# picotouch_synth.net
KiCad netlist of a schematic drawn in EAGLE
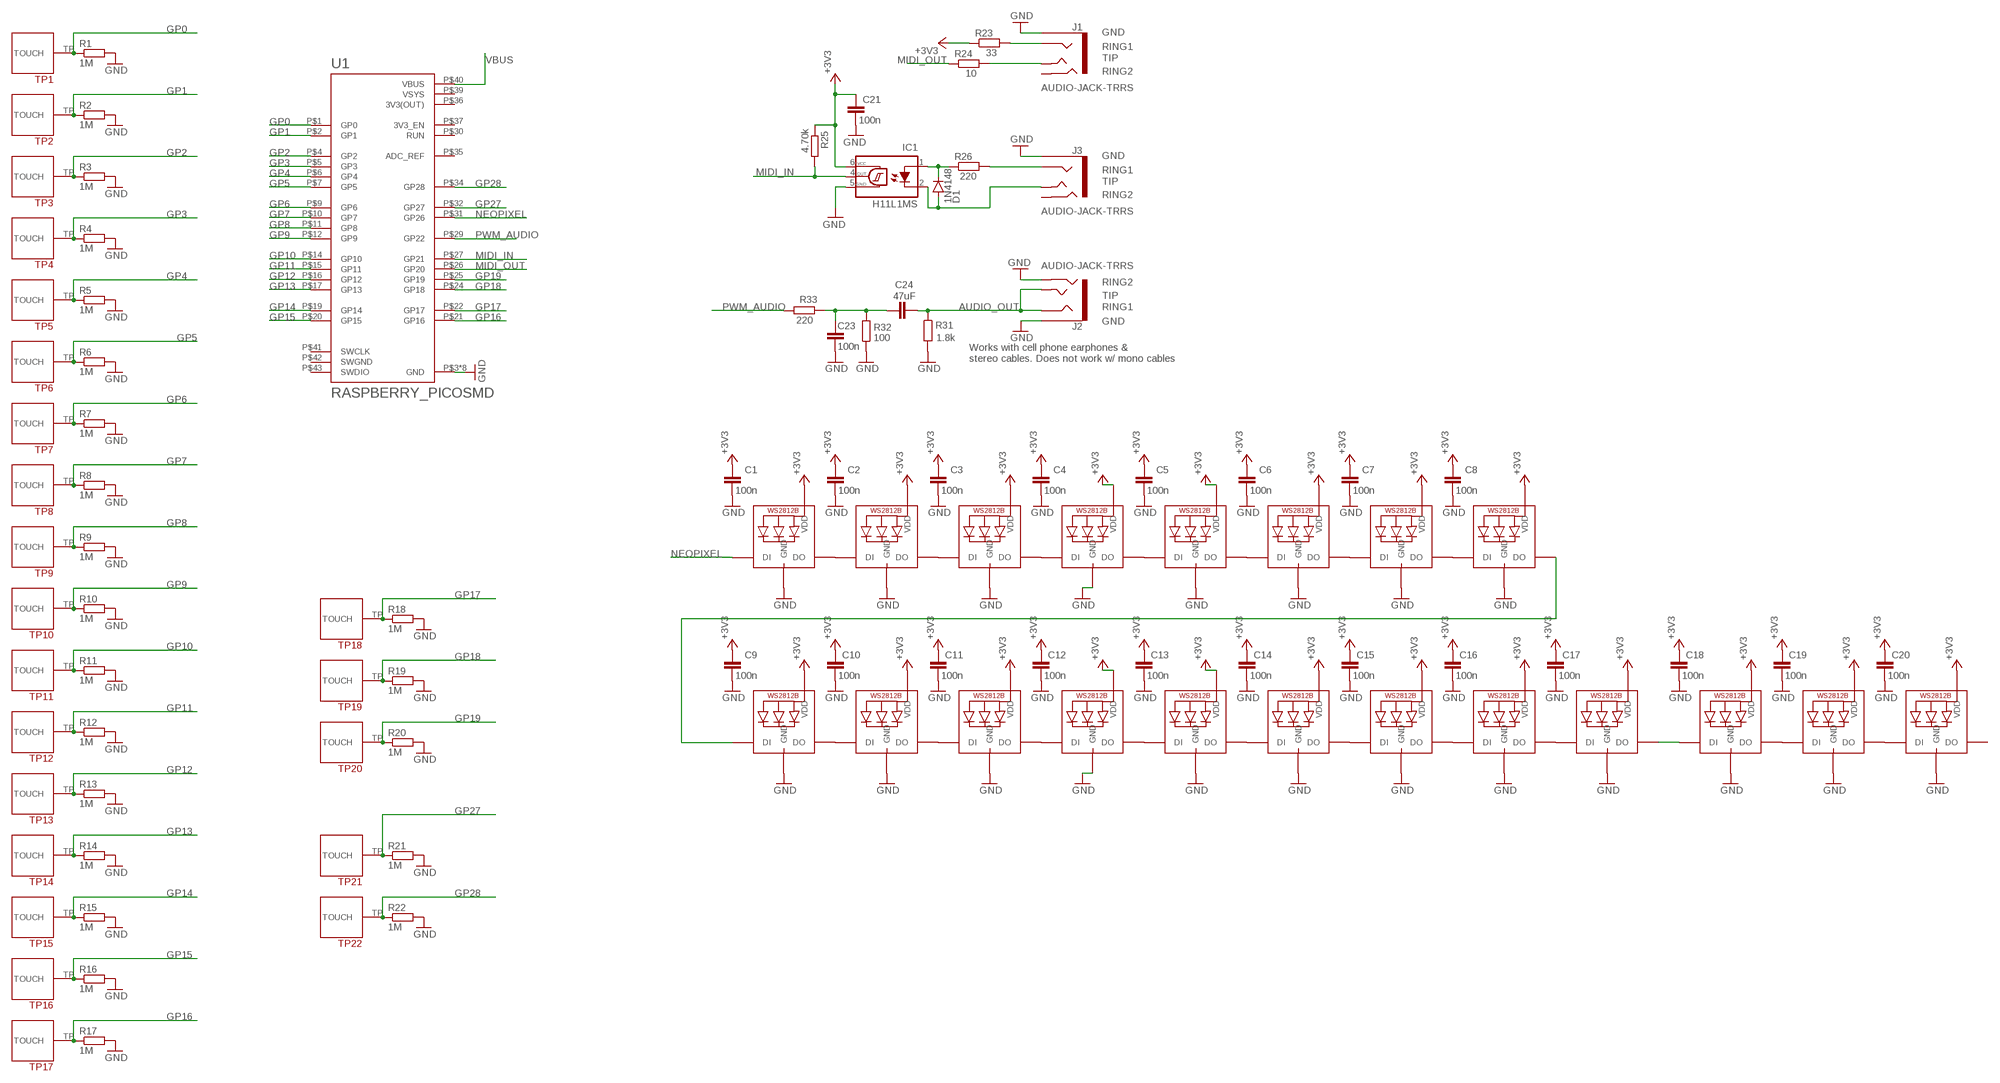
[diagram p0: schematic, sheet 1]

(export (version "E")
  (design (tool "Eeschema 10.0.6"))
  (components
    (comp (ref "C1")
      (value "100n")
      (footprint "eagle-import:C0603")
      (libsource (lib "eagle-import") (part "C-EUC0603"))
    )
    (comp (ref "C2")
      (value "100n")
      (footprint "eagle-import:C0603")
      (libsource (lib "eagle-import") (part "C-EUC0603"))
    )
    (comp (ref "C3")
      (value "100n")
      (footprint "eagle-import:C0603")
      (libsource (lib "eagle-import") (part "C-EUC0603"))
    )
    (comp (ref "C4")
      (value "100n")
      (footprint "eagle-import:C0603")
      (libsource (lib "eagle-import") (part "C-EUC0603"))
    )
    (comp (ref "C5")
      (value "100n")
      (footprint "eagle-import:C0603")
      (libsource (lib "eagle-import") (part "C-EUC0603"))
    )
    (comp (ref "C6")
      (value "100n")
      (footprint "eagle-import:C0603")
      (libsource (lib "eagle-import") (part "C-EUC0603"))
    )
    (comp (ref "C7")
      (value "100n")
      (footprint "eagle-import:C0603")
      (libsource (lib "eagle-import") (part "C-EUC0603"))
    )
    (comp (ref "C8")
      (value "100n")
      (footprint "eagle-import:C0603")
      (libsource (lib "eagle-import") (part "C-EUC0603"))
    )
    (comp (ref "C9")
      (value "100n")
      (footprint "eagle-import:C0603")
      (libsource (lib "eagle-import") (part "C-EUC0603"))
    )
    (comp (ref "C10")
      (value "100n")
      (footprint "eagle-import:C0603")
      (libsource (lib "eagle-import") (part "C-EUC0603"))
    )
    (comp (ref "C11")
      (value "100n")
      (footprint "eagle-import:C0603")
      (libsource (lib "eagle-import") (part "C-EUC0603"))
    )
    (comp (ref "C12")
      (value "100n")
      (footprint "eagle-import:C0603")
      (libsource (lib "eagle-import") (part "C-EUC0603"))
    )
    (comp (ref "C13")
      (value "100n")
      (footprint "eagle-import:C0603")
      (libsource (lib "eagle-import") (part "C-EUC0603"))
    )
    (comp (ref "C14")
      (value "100n")
      (footprint "eagle-import:C0603")
      (libsource (lib "eagle-import") (part "C-EUC0603"))
    )
    (comp (ref "C15")
      (value "100n")
      (footprint "eagle-import:C0603")
      (libsource (lib "eagle-import") (part "C-EUC0603"))
    )
    (comp (ref "C16")
      (value "100n")
      (footprint "eagle-import:C0603")
      (libsource (lib "eagle-import") (part "C-EUC0603"))
    )
    (comp (ref "C17")
      (value "100n")
      (footprint "eagle-import:C0603")
      (libsource (lib "eagle-import") (part "C-EUC0603"))
    )
    (comp (ref "C18")
      (value "100n")
      (footprint "eagle-import:C0603")
      (libsource (lib "eagle-import") (part "C-EUC0603"))
    )
    (comp (ref "C19")
      (value "100n")
      (footprint "eagle-import:C0603")
      (libsource (lib "eagle-import") (part "C-EUC0603"))
    )
    (comp (ref "C20")
      (value "100n")
      (footprint "eagle-import:C0603")
      (libsource (lib "eagle-import") (part "C-EUC0603"))
    )
    (comp (ref "C21")
      (value "100n")
      (footprint "eagle-import:C0603")
      (libsource (lib "eagle-import") (part "C-EUC0603"))
    )
    (comp (ref "C23")
      (value "100n")
      (footprint "eagle-import:C0603")
      (libsource (lib "eagle-import") (part "C-EUC0603"))
    )
    (comp (ref "C24")
      (value "47uF")
      (footprint "eagle-import:C0603")
      (libsource (lib "eagle-import") (part "C-EUC0603"))
    )
    (comp (ref "D1")
      (value "1N4148")
      (footprint "eagle-import:SOD123")
      (libsource (lib "eagle-import") (part "DIODE-SOD123"))
    )
    (comp (ref "IC1")
      (value "H11L1MS")
      (footprint "eagle-import:DIL6-SMD")
      (libsource (lib "eagle-import") (part "H11LMS1"))
    )
    (comp (ref "J1")
      (value "AUDIO-JACK-TRRS")
      (footprint "eagle-import:PJ-320D_SPARKFUN")
      (fields (field (name "MPN") "PJ-320D"))
      (libsource (lib "eagle-import") (part "AUDIO-JACK-TRRS"))
    )
    (comp (ref "J2")
      (value "AUDIO-JACK-TRRS")
      (footprint "eagle-import:PJ-320D_SPARKFUN")
      (fields (field (name "MPN") "PJ-320D") (field (name "LCSC") "C431535"))
      (libsource (lib "eagle-import") (part "AUDIO-JACK-TRRS"))
    )
    (comp (ref "J3")
      (value "AUDIO-JACK-TRRS")
      (footprint "eagle-import:PJ-320D_SPARKFUN")
      (fields (field (name "MPN") "PJ-320D"))
      (libsource (lib "eagle-import") (part "AUDIO-JACK-TRRS"))
    )
    (comp (ref "LED1")
      (value "WS2812B3535")
      (footprint "eagle-import:LED3535")
      (libsource (lib "eagle-import") (part "WS2812B3535"))
    )
    (comp (ref "LED2")
      (value "WS2812B3535")
      (footprint "eagle-import:LED3535")
      (libsource (lib "eagle-import") (part "WS2812B3535"))
    )
    (comp (ref "LED3")
      (value "WS2812B3535")
      (footprint "eagle-import:LED3535")
      (libsource (lib "eagle-import") (part "WS2812B3535"))
    )
    (comp (ref "LED4")
      (value "WS2812B3535")
      (footprint "eagle-import:LED3535")
      (libsource (lib "eagle-import") (part "WS2812B3535"))
    )
    (comp (ref "LED5")
      (value "WS2812B3535")
      (footprint "eagle-import:LED3535")
      (libsource (lib "eagle-import") (part "WS2812B3535"))
    )
    (comp (ref "LED6")
      (value "WS2812B3535")
      (footprint "eagle-import:LED3535")
      (libsource (lib "eagle-import") (part "WS2812B3535"))
    )
    (comp (ref "LED7")
      (value "WS2812B3535")
      (footprint "eagle-import:LED3535")
      (libsource (lib "eagle-import") (part "WS2812B3535"))
    )
    (comp (ref "LED8")
      (value "WS2812B3535")
      (footprint "eagle-import:LED3535")
      (libsource (lib "eagle-import") (part "WS2812B3535"))
    )
    (comp (ref "LED9")
      (value "WS2812B3535")
      (footprint "eagle-import:LED3535")
      (libsource (lib "eagle-import") (part "WS2812B3535"))
    )
    (comp (ref "LED10")
      (value "WS2812B3535")
      (footprint "eagle-import:LED3535")
      (libsource (lib "eagle-import") (part "WS2812B3535"))
    )
    (comp (ref "LED11")
      (value "WS2812B3535")
      (footprint "eagle-import:LED3535")
      (libsource (lib "eagle-import") (part "WS2812B3535"))
    )
    (comp (ref "LED12")
      (value "WS2812B3535")
      (footprint "eagle-import:LED3535")
      (libsource (lib "eagle-import") (part "WS2812B3535"))
    )
    (comp (ref "LED13")
      (value "WS2812B3535")
      (footprint "eagle-import:LED3535")
      (libsource (lib "eagle-import") (part "WS2812B3535"))
    )
    (comp (ref "LED14")
      (value "WS2812B3535")
      (footprint "eagle-import:LED3535")
      (libsource (lib "eagle-import") (part "WS2812B3535"))
    )
    (comp (ref "LED15")
      (value "WS2812B3535")
      (footprint "eagle-import:LED3535")
      (libsource (lib "eagle-import") (part "WS2812B3535"))
    )
    (comp (ref "LED16")
      (value "WS2812B3535")
      (footprint "eagle-import:LED3535")
      (libsource (lib "eagle-import") (part "WS2812B3535"))
    )
    (comp (ref "LED17")
      (value "WS2812B3535")
      (footprint "eagle-import:LED3535")
      (libsource (lib "eagle-import") (part "WS2812B3535"))
    )
    (comp (ref "LED18")
      (value "WS2812B3535")
      (footprint "eagle-import:LED3535")
      (libsource (lib "eagle-import") (part "WS2812B3535"))
    )
    (comp (ref "LED19")
      (value "WS2812B3535")
      (footprint "eagle-import:LED3535")
      (libsource (lib "eagle-import") (part "WS2812B3535"))
    )
    (comp (ref "LED20")
      (value "WS2812B3535")
      (footprint "eagle-import:LED3535")
      (libsource (lib "eagle-import") (part "WS2812B3535"))
    )
    (comp (ref "R1")
      (value "1M")
      (footprint "eagle-import:R0805")
      (libsource (lib "eagle-import") (part "R-EU_R0805"))
    )
    (comp (ref "R2")
      (value "1M")
      (footprint "eagle-import:R0805")
      (libsource (lib "eagle-import") (part "R-EU_R0805"))
    )
    (comp (ref "R3")
      (value "1M")
      (footprint "eagle-import:R0805")
      (libsource (lib "eagle-import") (part "R-EU_R0805"))
    )
    (comp (ref "R4")
      (value "1M")
      (footprint "eagle-import:R0805")
      (libsource (lib "eagle-import") (part "R-EU_R0805"))
    )
    (comp (ref "R5")
      (value "1M")
      (footprint "eagle-import:R0805")
      (libsource (lib "eagle-import") (part "R-EU_R0805"))
    )
    (comp (ref "R6")
      (value "1M")
      (footprint "eagle-import:R0805")
      (libsource (lib "eagle-import") (part "R-EU_R0805"))
    )
    (comp (ref "R7")
      (value "1M")
      (footprint "eagle-import:R0805")
      (libsource (lib "eagle-import") (part "R-EU_R0805"))
    )
    (comp (ref "R8")
      (value "1M")
      (footprint "eagle-import:R0805")
      (libsource (lib "eagle-import") (part "R-EU_R0805"))
    )
    (comp (ref "R9")
      (value "1M")
      (footprint "eagle-import:R0805")
      (libsource (lib "eagle-import") (part "R-EU_R0805"))
    )
    (comp (ref "R10")
      (value "1M")
      (footprint "eagle-import:R0805")
      (libsource (lib "eagle-import") (part "R-EU_R0805"))
    )
    (comp (ref "R11")
      (value "1M")
      (footprint "eagle-import:R0805")
      (libsource (lib "eagle-import") (part "R-EU_R0805"))
    )
    (comp (ref "R12")
      (value "1M")
      (footprint "eagle-import:R0805")
      (libsource (lib "eagle-import") (part "R-EU_R0805"))
    )
    (comp (ref "R13")
      (value "1M")
      (footprint "eagle-import:R0805")
      (libsource (lib "eagle-import") (part "R-EU_R0805"))
    )
    (comp (ref "R14")
      (value "1M")
      (footprint "eagle-import:R0805")
      (libsource (lib "eagle-import") (part "R-EU_R0805"))
    )
    (comp (ref "R15")
      (value "1M")
      (footprint "eagle-import:R0805")
      (libsource (lib "eagle-import") (part "R-EU_R0805"))
    )
    (comp (ref "R16")
      (value "1M")
      (footprint "eagle-import:R0805")
      (libsource (lib "eagle-import") (part "R-EU_R0805"))
    )
    (comp (ref "R17")
      (value "1M")
      (footprint "eagle-import:R0805")
      (libsource (lib "eagle-import") (part "R-EU_R0805"))
    )
    (comp (ref "R18")
      (value "1M")
      (footprint "eagle-import:R0603")
      (libsource (lib "eagle-import") (part "R-EU_R0603"))
    )
    (comp (ref "R19")
      (value "1M")
      (footprint "eagle-import:R0603")
      (libsource (lib "eagle-import") (part "R-EU_R0603"))
    )
    (comp (ref "R20")
      (value "1M")
      (footprint "eagle-import:R0603")
      (libsource (lib "eagle-import") (part "R-EU_R0603"))
    )
    (comp (ref "R21")
      (value "1M")
      (footprint "eagle-import:R0603")
      (libsource (lib "eagle-import") (part "R-EU_R0603"))
    )
    (comp (ref "R22")
      (value "1M")
      (footprint "eagle-import:R0603")
      (libsource (lib "eagle-import") (part "R-EU_R0603"))
    )
    (comp (ref "R23")
      (value "33")
      (footprint "eagle-import:R0603")
      (libsource (lib "eagle-import") (part "R-EU_R0603"))
    )
    (comp (ref "R24")
      (value "10")
      (footprint "eagle-import:R0603")
      (libsource (lib "eagle-import") (part "R-EU_R0603"))
    )
    (comp (ref "R25")
      (value "4.70k")
      (footprint "eagle-import:R0603")
      (libsource (lib "eagle-import") (part "R-EU_R0603"))
    )
    (comp (ref "R26")
      (value "220")
      (footprint "eagle-import:R0603")
      (libsource (lib "eagle-import") (part "R-EU_R0603"))
    )
    (comp (ref "R31")
      (value "1.8k")
      (footprint "eagle-import:R0603")
      (libsource (lib "eagle-import") (part "R-EU_R0603"))
    )
    (comp (ref "R32")
      (value "100")
      (footprint "eagle-import:R0603")
      (libsource (lib "eagle-import") (part "R-EU_R0603"))
    )
    (comp (ref "R33")
      (value "220")
      (footprint "eagle-import:R0603")
      (libsource (lib "eagle-import") (part "R-EU_R0603"))
    )
    (comp (ref "TP1")
      (value "TOUCHPADA")
      (footprint "eagle-import:TOUCHPADA")
      (libsource (lib "eagle-import") (part "TOUCHPADA"))
    )
    (comp (ref "TP2")
      (value "TOUCHPADA")
      (footprint "eagle-import:TOUCHPADA")
      (libsource (lib "eagle-import") (part "TOUCHPADA"))
    )
    (comp (ref "TP3")
      (value "TOUCHPADA")
      (footprint "eagle-import:TOUCHPADA")
      (libsource (lib "eagle-import") (part "TOUCHPADA"))
    )
    (comp (ref "TP4")
      (value "TOUCHPADA")
      (footprint "eagle-import:TOUCHPADA")
      (libsource (lib "eagle-import") (part "TOUCHPADA"))
    )
    (comp (ref "TP5")
      (value "TOUCHPADA")
      (footprint "eagle-import:TOUCHPADA")
      (libsource (lib "eagle-import") (part "TOUCHPADA"))
    )
    (comp (ref "TP6")
      (value "TOUCHPADA")
      (footprint "eagle-import:TOUCHPADA")
      (libsource (lib "eagle-import") (part "TOUCHPADA"))
    )
    (comp (ref "TP7")
      (value "TOUCHPADA")
      (footprint "eagle-import:TOUCHPADA")
      (libsource (lib "eagle-import") (part "TOUCHPADA"))
    )
    (comp (ref "TP8")
      (value "TOUCHPADA")
      (footprint "eagle-import:TOUCHPADA")
      (libsource (lib "eagle-import") (part "TOUCHPADA"))
    )
    (comp (ref "TP9")
      (value "TOUCHPADA")
      (footprint "eagle-import:TOUCHPADA")
      (libsource (lib "eagle-import") (part "TOUCHPADA"))
    )
    (comp (ref "TP10")
      (value "TOUCHPADA")
      (footprint "eagle-import:TOUCHPADA")
      (libsource (lib "eagle-import") (part "TOUCHPADA"))
    )
    (comp (ref "TP11")
      (value "TOUCHPADA")
      (footprint "eagle-import:TOUCHPADA")
      (libsource (lib "eagle-import") (part "TOUCHPADA"))
    )
    (comp (ref "TP12")
      (value "TOUCHPADA")
      (footprint "eagle-import:TOUCHPADA")
      (libsource (lib "eagle-import") (part "TOUCHPADA"))
    )
    (comp (ref "TP13")
      (value "TOUCHPADA")
      (footprint "eagle-import:TOUCHPADA")
      (libsource (lib "eagle-import") (part "TOUCHPADA"))
    )
    (comp (ref "TP14")
      (value "TOUCHPADA")
      (footprint "eagle-import:TOUCHPADA")
      (libsource (lib "eagle-import") (part "TOUCHPADA"))
    )
    (comp (ref "TP15")
      (value "TOUCHPADA")
      (footprint "eagle-import:TOUCHPADA")
      (libsource (lib "eagle-import") (part "TOUCHPADA"))
    )
    (comp (ref "TP16")
      (value "TOUCHPADA")
      (footprint "eagle-import:TOUCHPADA")
      (libsource (lib "eagle-import") (part "TOUCHPADA"))
    )
    (comp (ref "TP17")
      (value "TOUCHPADA")
      (footprint "eagle-import:TOUCHPADA")
      (libsource (lib "eagle-import") (part "TOUCHPADA"))
    )
    (comp (ref "TP18")
      (value "TOUCHPADB")
      (footprint "eagle-import:TOUCHPADB")
      (libsource (lib "eagle-import") (part "TOUCHPADB"))
    )
    (comp (ref "TP19")
      (value "TOUCHPADB")
      (footprint "eagle-import:TOUCHPADB")
      (libsource (lib "eagle-import") (part "TOUCHPADB"))
    )
    (comp (ref "TP20")
      (value "TOUCHPADB")
      (footprint "eagle-import:TOUCHPADB")
      (libsource (lib "eagle-import") (part "TOUCHPADB"))
    )
    (comp (ref "TP21")
      (value "TOUCHPADB")
      (footprint "eagle-import:TOUCHPADB")
      (libsource (lib "eagle-import") (part "TOUCHPADB"))
    )
    (comp (ref "TP22")
      (value "TOUCHPADB")
      (footprint "eagle-import:TOUCHPADB")
      (libsource (lib "eagle-import") (part "TOUCHPADB"))
    )
    (comp (ref "U1")
      (value "RASPBERRY_PICOSMD")
      (footprint "eagle-import:PICO-PKG-SMD")
      (libsource (lib "eagle-import") (part "RASPBERRY_PICOSMD"))
    )
  )
  (nets
    (net (code "1") (name "+3V3") (class "Default")
      (node (ref "C1") (pin "1") (pinfunction "1_1") (pintype "passive"))
      (node (ref "C10") (pin "1") (pinfunction "1_1") (pintype "passive"))
      (node (ref "C11") (pin "1") (pinfunction "1_1") (pintype "passive"))
      (node (ref "C12") (pin "1") (pinfunction "1_1") (pintype "passive"))
      (node (ref "C13") (pin "1") (pinfunction "1_1") (pintype "passive"))
      (node (ref "C14") (pin "1") (pinfunction "1_1") (pintype "passive"))
      (node (ref "C15") (pin "1") (pinfunction "1_1") (pintype "passive"))
      (node (ref "C16") (pin "1") (pinfunction "1_1") (pintype "passive"))
      (node (ref "C17") (pin "1") (pinfunction "1_1") (pintype "passive"))
      (node (ref "C18") (pin "1") (pinfunction "1_1") (pintype "passive"))
      (node (ref "C19") (pin "1") (pinfunction "1_1") (pintype "passive"))
      (node (ref "C2") (pin "1") (pinfunction "1_1") (pintype "passive"))
      (node (ref "C20") (pin "1") (pinfunction "1_1") (pintype "passive"))
      (node (ref "C21") (pin "1") (pinfunction "1_1") (pintype "passive"))
      (node (ref "C3") (pin "1") (pinfunction "1_1") (pintype "passive"))
      (node (ref "C4") (pin "1") (pinfunction "1_1") (pintype "passive"))
      (node (ref "C5") (pin "1") (pinfunction "1_1") (pintype "passive"))
      (node (ref "C6") (pin "1") (pinfunction "1_1") (pintype "passive"))
      (node (ref "C7") (pin "1") (pinfunction "1_1") (pintype "passive"))
      (node (ref "C8") (pin "1") (pinfunction "1_1") (pintype "passive"))
      (node (ref "C9") (pin "1") (pinfunction "1_1") (pintype "passive"))
      (node (ref "IC1") (pin "6") (pinfunction "VCC_6") (pintype "power_in"))
      (node (ref "LED1") (pin "2") (pinfunction "VDD_2") (pintype "power_in"))
      (node (ref "LED10") (pin "2") (pinfunction "VDD_2") (pintype "power_in"))
      (node (ref "LED11") (pin "2") (pinfunction "VDD_2") (pintype "power_in"))
      (node (ref "LED12") (pin "2") (pinfunction "VDD_2") (pintype "power_in"))
      (node (ref "LED13") (pin "2") (pinfunction "VDD_2") (pintype "power_in"))
      (node (ref "LED14") (pin "2") (pinfunction "VDD_2") (pintype "power_in"))
      (node (ref "LED15") (pin "2") (pinfunction "VDD_2") (pintype "power_in"))
      (node (ref "LED16") (pin "2") (pinfunction "VDD_2") (pintype "power_in"))
      (node (ref "LED17") (pin "2") (pinfunction "VDD_2") (pintype "power_in"))
      (node (ref "LED18") (pin "2") (pinfunction "VDD_2") (pintype "power_in"))
      (node (ref "LED19") (pin "2") (pinfunction "VDD_2") (pintype "power_in"))
      (node (ref "LED2") (pin "2") (pinfunction "VDD_2") (pintype "power_in"))
      (node (ref "LED20") (pin "2") (pinfunction "VDD_2") (pintype "power_in"))
      (node (ref "LED3") (pin "2") (pinfunction "VDD_2") (pintype "power_in"))
      (node (ref "LED4") (pin "2") (pinfunction "VDD_2") (pintype "power_in"))
      (node (ref "LED5") (pin "2") (pinfunction "VDD_2") (pintype "power_in"))
      (node (ref "LED6") (pin "2") (pinfunction "VDD_2") (pintype "power_in"))
      (node (ref "LED7") (pin "2") (pinfunction "VDD_2") (pintype "power_in"))
      (node (ref "LED8") (pin "2") (pinfunction "VDD_2") (pintype "power_in"))
      (node (ref "LED9") (pin "2") (pinfunction "VDD_2") (pintype "power_in"))
      (node (ref "R23") (pin "1") (pinfunction "1_1") (pintype "passive"))
      (node (ref "R25") (pin "1") (pinfunction "1_1") (pintype "passive"))
    )
    (net (code "2") (name "/3V3(OUT)") (class "Default")
      (node (ref "U1") (pin "P$36") (pinfunction "3V3(OUT)_P$36") (pintype "power_in"))
    )
    (net (code "3") (name "/AUDIO_OUT") (class "Default")
      (node (ref "C24") (pin "2") (pinfunction "2_2") (pintype "passive"))
      (node (ref "J2") (pin "RING1") (pinfunction "RING1_RING1") (pintype "bidirectional"))
      (node (ref "J2") (pin "TIP") (pinfunction "TIP_TIP") (pintype "bidirectional"))
      (node (ref "R31") (pin "1") (pinfunction "1_1") (pintype "passive"))
    )
    (net (code "4") (name "/GP0") (class "Default")
      (node (ref "R1") (pin "1") (pinfunction "1_1") (pintype "passive"))
      (node (ref "TP1") (pin "TP") (pinfunction "TOUCH_TP") (pintype "bidirectional"))
      (node (ref "U1") (pin "P$1") (pinfunction "GP0_P$1") (pintype "bidirectional"))
    )
    (net (code "5") (name "/GP1") (class "Default")
      (node (ref "R2") (pin "1") (pinfunction "1_1") (pintype "passive"))
      (node (ref "TP2") (pin "TP") (pinfunction "TOUCH_TP") (pintype "bidirectional"))
      (node (ref "U1") (pin "P$2") (pinfunction "GP1_P$2") (pintype "bidirectional"))
    )
    (net (code "6") (name "/GP2") (class "Default")
      (node (ref "R3") (pin "1") (pinfunction "1_1") (pintype "passive"))
      (node (ref "TP3") (pin "TP") (pinfunction "TOUCH_TP") (pintype "bidirectional"))
      (node (ref "U1") (pin "P$4") (pinfunction "GP2_P$4") (pintype "bidirectional"))
    )
    (net (code "7") (name "/GP3") (class "Default")
      (node (ref "R4") (pin "1") (pinfunction "1_1") (pintype "passive"))
      (node (ref "TP4") (pin "TP") (pinfunction "TOUCH_TP") (pintype "bidirectional"))
      (node (ref "U1") (pin "P$5") (pinfunction "GP3_P$5") (pintype "bidirectional"))
    )
    (net (code "8") (name "/GP4") (class "Default")
      (node (ref "R5") (pin "1") (pinfunction "1_1") (pintype "passive"))
      (node (ref "TP5") (pin "TP") (pinfunction "TOUCH_TP") (pintype "bidirectional"))
      (node (ref "U1") (pin "P$6") (pinfunction "GP4_P$6") (pintype "bidirectional"))
    )
    (net (code "9") (name "/GP5") (class "Default")
      (node (ref "R6") (pin "1") (pinfunction "1_1") (pintype "passive"))
      (node (ref "TP6") (pin "TP") (pinfunction "TOUCH_TP") (pintype "bidirectional"))
      (node (ref "U1") (pin "P$7") (pinfunction "GP5_P$7") (pintype "bidirectional"))
    )
    (net (code "10") (name "/GP6") (class "Default")
      (node (ref "R7") (pin "1") (pinfunction "1_1") (pintype "passive"))
      (node (ref "TP7") (pin "TP") (pinfunction "TOUCH_TP") (pintype "bidirectional"))
      (node (ref "U1") (pin "P$9") (pinfunction "GP6_P$9") (pintype "bidirectional"))
    )
    (net (code "11") (name "/GP7") (class "Default")
      (node (ref "R8") (pin "1") (pinfunction "1_1") (pintype "passive"))
      (node (ref "TP8") (pin "TP") (pinfunction "TOUCH_TP") (pintype "bidirectional"))
      (node (ref "U1") (pin "P$10") (pinfunction "GP7_P$10") (pintype "bidirectional"))
    )
    (net (code "12") (name "/GP8") (class "Default")
      (node (ref "R9") (pin "1") (pinfunction "1_1") (pintype "passive"))
      (node (ref "TP9") (pin "TP") (pinfunction "TOUCH_TP") (pintype "bidirectional"))
      (node (ref "U1") (pin "P$11") (pinfunction "GP8_P$11") (pintype "bidirectional"))
    )
    (net (code "13") (name "/GP9") (class "Default")
      (node (ref "R10") (pin "1") (pinfunction "1_1") (pintype "passive"))
      (node (ref "TP10") (pin "TP") (pinfunction "TOUCH_TP") (pintype "bidirectional"))
      (node (ref "U1") (pin "P$12") (pinfunction "GP9_P$12") (pintype "bidirectional"))
    )
    (net (code "14") (name "/GP10") (class "Default")
      (node (ref "R11") (pin "1") (pinfunction "1_1") (pintype "passive"))
      (node (ref "TP11") (pin "TP") (pinfunction "TOUCH_TP") (pintype "bidirectional"))
      (node (ref "U1") (pin "P$14") (pinfunction "GP10_P$14") (pintype "bidirectional"))
    )
    (net (code "15") (name "/GP11") (class "Default")
      (node (ref "R12") (pin "1") (pinfunction "1_1") (pintype "passive"))
      (node (ref "TP12") (pin "TP") (pinfunction "TOUCH_TP") (pintype "bidirectional"))
      (node (ref "U1") (pin "P$15") (pinfunction "GP11_P$15") (pintype "bidirectional"))
    )
    (net (code "16") (name "/GP12") (class "Default")
      (node (ref "R13") (pin "1") (pinfunction "1_1") (pintype "passive"))
      (node (ref "TP13") (pin "TP") (pinfunction "TOUCH_TP") (pintype "bidirectional"))
      (node (ref "U1") (pin "P$16") (pinfunction "GP12_P$16") (pintype "bidirectional"))
    )
    (net (code "17") (name "/GP13") (class "Default")
      (node (ref "R14") (pin "1") (pinfunction "1_1") (pintype "passive"))
      (node (ref "TP14") (pin "TP") (pinfunction "TOUCH_TP") (pintype "bidirectional"))
      (node (ref "U1") (pin "P$17") (pinfunction "GP13_P$17") (pintype "bidirectional"))
    )
    (net (code "18") (name "/GP14") (class "Default")
      (node (ref "R15") (pin "1") (pinfunction "1_1") (pintype "passive"))
      (node (ref "TP15") (pin "TP") (pinfunction "TOUCH_TP") (pintype "bidirectional"))
      (node (ref "U1") (pin "P$19") (pinfunction "GP14_P$19") (pintype "bidirectional"))
    )
    (net (code "19") (name "/GP15") (class "Default")
      (node (ref "R16") (pin "1") (pinfunction "1_1") (pintype "passive"))
      (node (ref "TP16") (pin "TP") (pinfunction "TOUCH_TP") (pintype "bidirectional"))
      (node (ref "U1") (pin "P$20") (pinfunction "GP15_P$20") (pintype "bidirectional"))
    )
    (net (code "20") (name "/GP16") (class "Default")
      (node (ref "R17") (pin "1") (pinfunction "1_1") (pintype "passive"))
      (node (ref "TP17") (pin "TP") (pinfunction "TOUCH_TP") (pintype "bidirectional"))
      (node (ref "U1") (pin "P$21") (pinfunction "GP16_P$21") (pintype "bidirectional"))
    )
    (net (code "21") (name "/GP17") (class "Default")
      (node (ref "R18") (pin "1") (pinfunction "1_1") (pintype "passive"))
      (node (ref "TP18") (pin "TP") (pinfunction "TOUCH_TP") (pintype "bidirectional"))
      (node (ref "U1") (pin "P$22") (pinfunction "GP17_P$22") (pintype "bidirectional"))
    )
    (net (code "22") (name "/GP18") (class "Default")
      (node (ref "R19") (pin "1") (pinfunction "1_1") (pintype "passive"))
      (node (ref "TP19") (pin "TP") (pinfunction "TOUCH_TP") (pintype "bidirectional"))
      (node (ref "U1") (pin "P$24") (pinfunction "GP18_P$24") (pintype "bidirectional"))
    )
    (net (code "23") (name "/GP19") (class "Default")
      (node (ref "R20") (pin "1") (pinfunction "1_1") (pintype "passive"))
      (node (ref "TP20") (pin "TP") (pinfunction "TOUCH_TP") (pintype "bidirectional"))
      (node (ref "U1") (pin "P$25") (pinfunction "GP19_P$25") (pintype "bidirectional"))
    )
    (net (code "24") (name "/GP27") (class "Default")
      (node (ref "R21") (pin "1") (pinfunction "1_1") (pintype "passive"))
      (node (ref "TP21") (pin "TP") (pinfunction "TOUCH_TP") (pintype "bidirectional"))
      (node (ref "U1") (pin "P$32") (pinfunction "GP27_P$32") (pintype "bidirectional"))
    )
    (net (code "25") (name "/GP28") (class "Default")
      (node (ref "R22") (pin "1") (pinfunction "1_1") (pintype "passive"))
      (node (ref "TP22") (pin "TP") (pinfunction "TOUCH_TP") (pintype "bidirectional"))
      (node (ref "U1") (pin "P$34") (pinfunction "GP28_P$34") (pintype "bidirectional"))
    )
    (net (code "26") (name "/MIDI_IN") (class "Default")
      (node (ref "IC1") (pin "4") (pinfunction "OUT_4") (pintype "output"))
      (node (ref "R25") (pin "2") (pinfunction "2_2") (pintype "passive"))
      (node (ref "U1") (pin "P$27") (pinfunction "GP21_P$27") (pintype "bidirectional"))
    )
    (net (code "27") (name "/MIDI_OUT") (class "Default")
      (node (ref "R24") (pin "1") (pinfunction "1_1") (pintype "passive"))
      (node (ref "U1") (pin "P$26") (pinfunction "GP20_P$26") (pintype "bidirectional"))
    )
    (net (code "28") (name "/NEOPIXEL") (class "Default")
      (node (ref "LED1") (pin "1") (pinfunction "DI_1") (pintype "input"))
      (node (ref "U1") (pin "P$31") (pinfunction "GP26_P$31") (pintype "bidirectional"))
    )
    (net (code "29") (name "/PWM_AUDIO") (class "Default")
      (node (ref "R33") (pin "2") (pinfunction "2_2") (pintype "passive"))
      (node (ref "U1") (pin "P$29") (pinfunction "GP22_P$29") (pintype "bidirectional"))
    )
    (net (code "30") (name "/SWGND") (class "Default")
      (node (ref "U1") (pin "P$42") (pinfunction "SWGND_P$42") (pintype "power_in"))
    )
    (net (code "31") (name "/VBUS") (class "Default")
      (node (ref "U1") (pin "P$40") (pinfunction "VBUS_P$40") (pintype "power_in"))
    )
    (net (code "32") (name "/VSYS") (class "Default")
      (node (ref "U1") (pin "P$39") (pinfunction "VSYS_P$39") (pintype "power_in"))
    )
    (net (code "33") (name "GND") (class "Default")
      (node (ref "C1") (pin "2") (pinfunction "2_2") (pintype "passive"))
      (node (ref "C10") (pin "2") (pinfunction "2_2") (pintype "passive"))
      (node (ref "C11") (pin "2") (pinfunction "2_2") (pintype "passive"))
      (node (ref "C12") (pin "2") (pinfunction "2_2") (pintype "passive"))
      (node (ref "C13") (pin "2") (pinfunction "2_2") (pintype "passive"))
      (node (ref "C14") (pin "2") (pinfunction "2_2") (pintype "passive"))
      (node (ref "C15") (pin "2") (pinfunction "2_2") (pintype "passive"))
      (node (ref "C16") (pin "2") (pinfunction "2_2") (pintype "passive"))
      (node (ref "C17") (pin "2") (pinfunction "2_2") (pintype "passive"))
      (node (ref "C18") (pin "2") (pinfunction "2_2") (pintype "passive"))
      (node (ref "C19") (pin "2") (pinfunction "2_2") (pintype "passive"))
      (node (ref "C2") (pin "2") (pinfunction "2_2") (pintype "passive"))
      (node (ref "C20") (pin "2") (pinfunction "2_2") (pintype "passive"))
      (node (ref "C21") (pin "2") (pinfunction "2_2") (pintype "passive"))
      (node (ref "C23") (pin "2") (pinfunction "2_2") (pintype "passive"))
      (node (ref "C3") (pin "2") (pinfunction "2_2") (pintype "passive"))
      (node (ref "C4") (pin "2") (pinfunction "2_2") (pintype "passive"))
      (node (ref "C5") (pin "2") (pinfunction "2_2") (pintype "passive"))
      (node (ref "C6") (pin "2") (pinfunction "2_2") (pintype "passive"))
      (node (ref "C7") (pin "2") (pinfunction "2_2") (pintype "passive"))
      (node (ref "C8") (pin "2") (pinfunction "2_2") (pintype "passive"))
      (node (ref "C9") (pin "2") (pinfunction "2_2") (pintype "passive"))
      (node (ref "IC1") (pin "5") (pinfunction "GND_5") (pintype "power_in"))
      (node (ref "J1") (pin "EARTH") (pinfunction "EARTH_EARTH") (pintype "bidirectional"))
      (node (ref "J2") (pin "EARTH") (pinfunction "EARTH_EARTH") (pintype "bidirectional"))
      (node (ref "J2") (pin "RING2") (pinfunction "RING2_RING2") (pintype "bidirectional"))
      (node (ref "J3") (pin "EARTH") (pinfunction "EARTH_EARTH") (pintype "bidirectional"))
      (node (ref "LED1") (pin "4") (pinfunction "GND_4") (pintype "power_in"))
      (node (ref "LED10") (pin "4") (pinfunction "GND_4") (pintype "power_in"))
      (node (ref "LED11") (pin "4") (pinfunction "GND_4") (pintype "power_in"))
      (node (ref "LED12") (pin "4") (pinfunction "GND_4") (pintype "power_in"))
      (node (ref "LED13") (pin "4") (pinfunction "GND_4") (pintype "power_in"))
      (node (ref "LED14") (pin "4") (pinfunction "GND_4") (pintype "power_in"))
      (node (ref "LED15") (pin "4") (pinfunction "GND_4") (pintype "power_in"))
      (node (ref "LED16") (pin "4") (pinfunction "GND_4") (pintype "power_in"))
      (node (ref "LED17") (pin "4") (pinfunction "GND_4") (pintype "power_in"))
      (node (ref "LED18") (pin "4") (pinfunction "GND_4") (pintype "power_in"))
      (node (ref "LED19") (pin "4") (pinfunction "GND_4") (pintype "power_in"))
      (node (ref "LED2") (pin "4") (pinfunction "GND_4") (pintype "power_in"))
      (node (ref "LED20") (pin "4") (pinfunction "GND_4") (pintype "power_in"))
      (node (ref "LED3") (pin "4") (pinfunction "GND_4") (pintype "power_in"))
      (node (ref "LED4") (pin "4") (pinfunction "GND_4") (pintype "power_in"))
      (node (ref "LED5") (pin "4") (pinfunction "GND_4") (pintype "power_in"))
      (node (ref "LED6") (pin "4") (pinfunction "GND_4") (pintype "power_in"))
      (node (ref "LED7") (pin "4") (pinfunction "GND_4") (pintype "power_in"))
      (node (ref "LED8") (pin "4") (pinfunction "GND_4") (pintype "power_in"))
      (node (ref "LED9") (pin "4") (pinfunction "GND_4") (pintype "power_in"))
      (node (ref "R1") (pin "2") (pinfunction "2_2") (pintype "passive"))
      (node (ref "R10") (pin "2") (pinfunction "2_2") (pintype "passive"))
      (node (ref "R11") (pin "2") (pinfunction "2_2") (pintype "passive"))
      (node (ref "R12") (pin "2") (pinfunction "2_2") (pintype "passive"))
      (node (ref "R13") (pin "2") (pinfunction "2_2") (pintype "passive"))
      (node (ref "R14") (pin "2") (pinfunction "2_2") (pintype "passive"))
      (node (ref "R15") (pin "2") (pinfunction "2_2") (pintype "passive"))
      (node (ref "R16") (pin "2") (pinfunction "2_2") (pintype "passive"))
      (node (ref "R17") (pin "2") (pinfunction "2_2") (pintype "passive"))
      (node (ref "R18") (pin "2") (pinfunction "2_2") (pintype "passive"))
      (node (ref "R19") (pin "2") (pinfunction "2_2") (pintype "passive"))
      (node (ref "R2") (pin "2") (pinfunction "2_2") (pintype "passive"))
      (node (ref "R20") (pin "2") (pinfunction "2_2") (pintype "passive"))
      (node (ref "R21") (pin "2") (pinfunction "2_2") (pintype "passive"))
      (node (ref "R22") (pin "2") (pinfunction "2_2") (pintype "passive"))
      (node (ref "R3") (pin "2") (pinfunction "2_2") (pintype "passive"))
      (node (ref "R31") (pin "2") (pinfunction "2_2") (pintype "passive"))
      (node (ref "R32") (pin "1") (pinfunction "1_1") (pintype "passive"))
      (node (ref "R4") (pin "2") (pinfunction "2_2") (pintype "passive"))
      (node (ref "R5") (pin "2") (pinfunction "2_2") (pintype "passive"))
      (node (ref "R6") (pin "2") (pinfunction "2_2") (pintype "passive"))
      (node (ref "R7") (pin "2") (pinfunction "2_2") (pintype "passive"))
      (node (ref "R8") (pin "2") (pinfunction "2_2") (pintype "passive"))
      (node (ref "R9") (pin "2") (pinfunction "2_2") (pintype "passive"))
      (node (ref "U1") (pin "P$13") (pinfunction "GND_P$13") (pintype "power_in"))
      (node (ref "U1") (pin "P$18") (pinfunction "GND_P$18") (pintype "power_in"))
      (node (ref "U1") (pin "P$23") (pinfunction "GND_P$23") (pintype "power_in"))
      (node (ref "U1") (pin "P$28") (pinfunction "GND_P$28") (pintype "power_in"))
      (node (ref "U1") (pin "P$3") (pinfunction "GND_P$3") (pintype "power_in"))
      (node (ref "U1") (pin "P$33") (pinfunction "GND_P$33") (pintype "power_in"))
      (node (ref "U1") (pin "P$38") (pinfunction "GND_P$38") (pintype "power_in"))
      (node (ref "U1") (pin "P$8") (pinfunction "GND_P$8") (pintype "power_in"))
    )
    (net (code "34") (name "Net-(C23-Pad1)") (class "Default")
      (node (ref "C23") (pin "1") (pinfunction "1_1") (pintype "passive"))
      (node (ref "C24") (pin "1") (pinfunction "1_1") (pintype "passive"))
      (node (ref "R32") (pin "2") (pinfunction "2_2") (pintype "passive"))
      (node (ref "R33") (pin "1") (pinfunction "1_1") (pintype "passive"))
    )
    (net (code "35") (name "Net-(IC1-A)") (class "Default")
      (node (ref "D1") (pin "C") (pinfunction "C_C") (pintype "passive"))
      (node (ref "IC1") (pin "1") (pinfunction "A_1") (pintype "passive"))
      (node (ref "R26") (pin "1") (pinfunction "1_1") (pintype "passive"))
    )
    (net (code "36") (name "Net-(IC1-C)") (class "Default")
      (node (ref "D1") (pin "A") (pinfunction "A_A") (pintype "passive"))
      (node (ref "IC1") (pin "2") (pinfunction "C_2") (pintype "passive"))
      (node (ref "J3") (pin "TIP") (pinfunction "TIP_TIP") (pintype "bidirectional"))
    )
    (net (code "37") (name "Net-(J1-PadRING1)") (class "Default")
      (node (ref "J1") (pin "RING1") (pinfunction "RING1_RING1") (pintype "bidirectional"))
      (node (ref "R23") (pin "2") (pinfunction "2_2") (pintype "passive"))
    )
    (net (code "38") (name "Net-(J1-PadTIP)") (class "Default")
      (node (ref "J1") (pin "TIP") (pinfunction "TIP_TIP") (pintype "bidirectional"))
      (node (ref "R24") (pin "2") (pinfunction "2_2") (pintype "passive"))
    )
    (net (code "39") (name "Net-(J3-PadRING1)") (class "Default")
      (node (ref "J3") (pin "RING1") (pinfunction "RING1_RING1") (pintype "bidirectional"))
      (node (ref "R26") (pin "2") (pinfunction "2_2") (pintype "passive"))
    )
    (net (code "40") (name "Net-(LED1-DO)") (class "Default")
      (node (ref "LED1") (pin "3") (pinfunction "DO_3") (pintype "output"))
      (node (ref "LED2") (pin "1") (pinfunction "DI_1") (pintype "input"))
    )
    (net (code "41") (name "Net-(LED2-DO)") (class "Default")
      (node (ref "LED2") (pin "3") (pinfunction "DO_3") (pintype "output"))
      (node (ref "LED3") (pin "1") (pinfunction "DI_1") (pintype "input"))
    )
    (net (code "42") (name "Net-(LED3-DO)") (class "Default")
      (node (ref "LED3") (pin "3") (pinfunction "DO_3") (pintype "output"))
      (node (ref "LED4") (pin "1") (pinfunction "DI_1") (pintype "input"))
    )
    (net (code "43") (name "Net-(LED4-DO)") (class "Default")
      (node (ref "LED4") (pin "3") (pinfunction "DO_3") (pintype "output"))
      (node (ref "LED5") (pin "1") (pinfunction "DI_1") (pintype "input"))
    )
    (net (code "44") (name "Net-(LED5-DO)") (class "Default")
      (node (ref "LED5") (pin "3") (pinfunction "DO_3") (pintype "output"))
      (node (ref "LED6") (pin "1") (pinfunction "DI_1") (pintype "input"))
    )
    (net (code "45") (name "Net-(LED6-DO)") (class "Default")
      (node (ref "LED6") (pin "3") (pinfunction "DO_3") (pintype "output"))
      (node (ref "LED7") (pin "1") (pinfunction "DI_1") (pintype "input"))
    )
    (net (code "46") (name "Net-(LED7-DO)") (class "Default")
      (node (ref "LED7") (pin "3") (pinfunction "DO_3") (pintype "output"))
      (node (ref "LED8") (pin "1") (pinfunction "DI_1") (pintype "input"))
    )
    (net (code "47") (name "Net-(LED8-DO)") (class "Default")
      (node (ref "LED8") (pin "3") (pinfunction "DO_3") (pintype "output"))
      (node (ref "LED9") (pin "1") (pinfunction "DI_1") (pintype "input"))
    )
    (net (code "48") (name "Net-(LED10-DI)") (class "Default")
      (node (ref "LED10") (pin "1") (pinfunction "DI_1") (pintype "input"))
      (node (ref "LED9") (pin "3") (pinfunction "DO_3") (pintype "output"))
    )
    (net (code "49") (name "Net-(LED10-DO)") (class "Default")
      (node (ref "LED10") (pin "3") (pinfunction "DO_3") (pintype "output"))
      (node (ref "LED11") (pin "1") (pinfunction "DI_1") (pintype "input"))
    )
    (net (code "50") (name "Net-(LED11-DO)") (class "Default")
      (node (ref "LED11") (pin "3") (pinfunction "DO_3") (pintype "output"))
      (node (ref "LED12") (pin "1") (pinfunction "DI_1") (pintype "input"))
    )
    (net (code "51") (name "Net-(LED12-DO)") (class "Default")
      (node (ref "LED12") (pin "3") (pinfunction "DO_3") (pintype "output"))
      (node (ref "LED13") (pin "1") (pinfunction "DI_1") (pintype "input"))
    )
    (net (code "52") (name "Net-(LED13-DO)") (class "Default")
      (node (ref "LED13") (pin "3") (pinfunction "DO_3") (pintype "output"))
      (node (ref "LED14") (pin "1") (pinfunction "DI_1") (pintype "input"))
    )
    (net (code "53") (name "Net-(LED14-DO)") (class "Default")
      (node (ref "LED14") (pin "3") (pinfunction "DO_3") (pintype "output"))
      (node (ref "LED15") (pin "1") (pinfunction "DI_1") (pintype "input"))
    )
    (net (code "54") (name "Net-(LED15-DO)") (class "Default")
      (node (ref "LED15") (pin "3") (pinfunction "DO_3") (pintype "output"))
      (node (ref "LED16") (pin "1") (pinfunction "DI_1") (pintype "input"))
    )
    (net (code "55") (name "Net-(LED16-DO)") (class "Default")
      (node (ref "LED16") (pin "3") (pinfunction "DO_3") (pintype "output"))
      (node (ref "LED17") (pin "1") (pinfunction "DI_1") (pintype "input"))
    )
    (net (code "56") (name "Net-(LED17-DO)") (class "Default")
      (node (ref "LED17") (pin "3") (pinfunction "DO_3") (pintype "output"))
      (node (ref "LED18") (pin "1") (pinfunction "DI_1") (pintype "input"))
    )
    (net (code "57") (name "Net-(LED18-DO)") (class "Default")
      (node (ref "LED18") (pin "3") (pinfunction "DO_3") (pintype "output"))
      (node (ref "LED19") (pin "1") (pinfunction "DI_1") (pintype "input"))
    )
    (net (code "58") (name "Net-(LED19-DO)") (class "Default")
      (node (ref "LED19") (pin "3") (pinfunction "DO_3") (pintype "output"))
      (node (ref "LED20") (pin "1") (pinfunction "DI_1") (pintype "input"))
    )
    (net (code "59") (name "unconnected-(J1-PadRING2)") (class "Default")
      (node (ref "J1") (pin "RING2") (pinfunction "RING2_RING2") (pintype "bidirectional"))
    )
    (net (code "60") (name "unconnected-(J3-PadRING2)") (class "Default")
      (node (ref "J3") (pin "RING2") (pinfunction "RING2_RING2") (pintype "bidirectional"))
    )
    (net (code "61") (name "unconnected-(LED20-DO-Pad3)") (class "Default")
      (node (ref "LED20") (pin "3") (pinfunction "DO_3") (pintype "output"))
    )
    (net (code "62") (name "unconnected-(U1-3V3_EN-PadP$37)") (class "Default")
      (node (ref "U1") (pin "P$37") (pinfunction "3V3_EN_P$37") (pintype "input"))
    )
    (net (code "63") (name "unconnected-(U1-ADC_REF-PadP$35)") (class "Default")
      (node (ref "U1") (pin "P$35") (pinfunction "ADC_REF_P$35") (pintype "input"))
    )
    (net (code "64") (name "unconnected-(U1-RUN-PadP$30)") (class "Default")
      (node (ref "U1") (pin "P$30") (pinfunction "RUN_P$30") (pintype "input"))
    )
    (net (code "65") (name "unconnected-(U1-SWCLK-PadP$41)") (class "Default")
      (node (ref "U1") (pin "P$41") (pinfunction "SWCLK_P$41") (pintype "input"))
    )
    (net (code "66") (name "unconnected-(U1-SWDIO-PadP$43)") (class "Default")
      (node (ref "U1") (pin "P$43") (pinfunction "SWDIO_P$43") (pintype "bidirectional"))
    )
  )
)
